# HoneyBee-V1_1.net
KiCad netlist of a schematic drawn in EAGLE
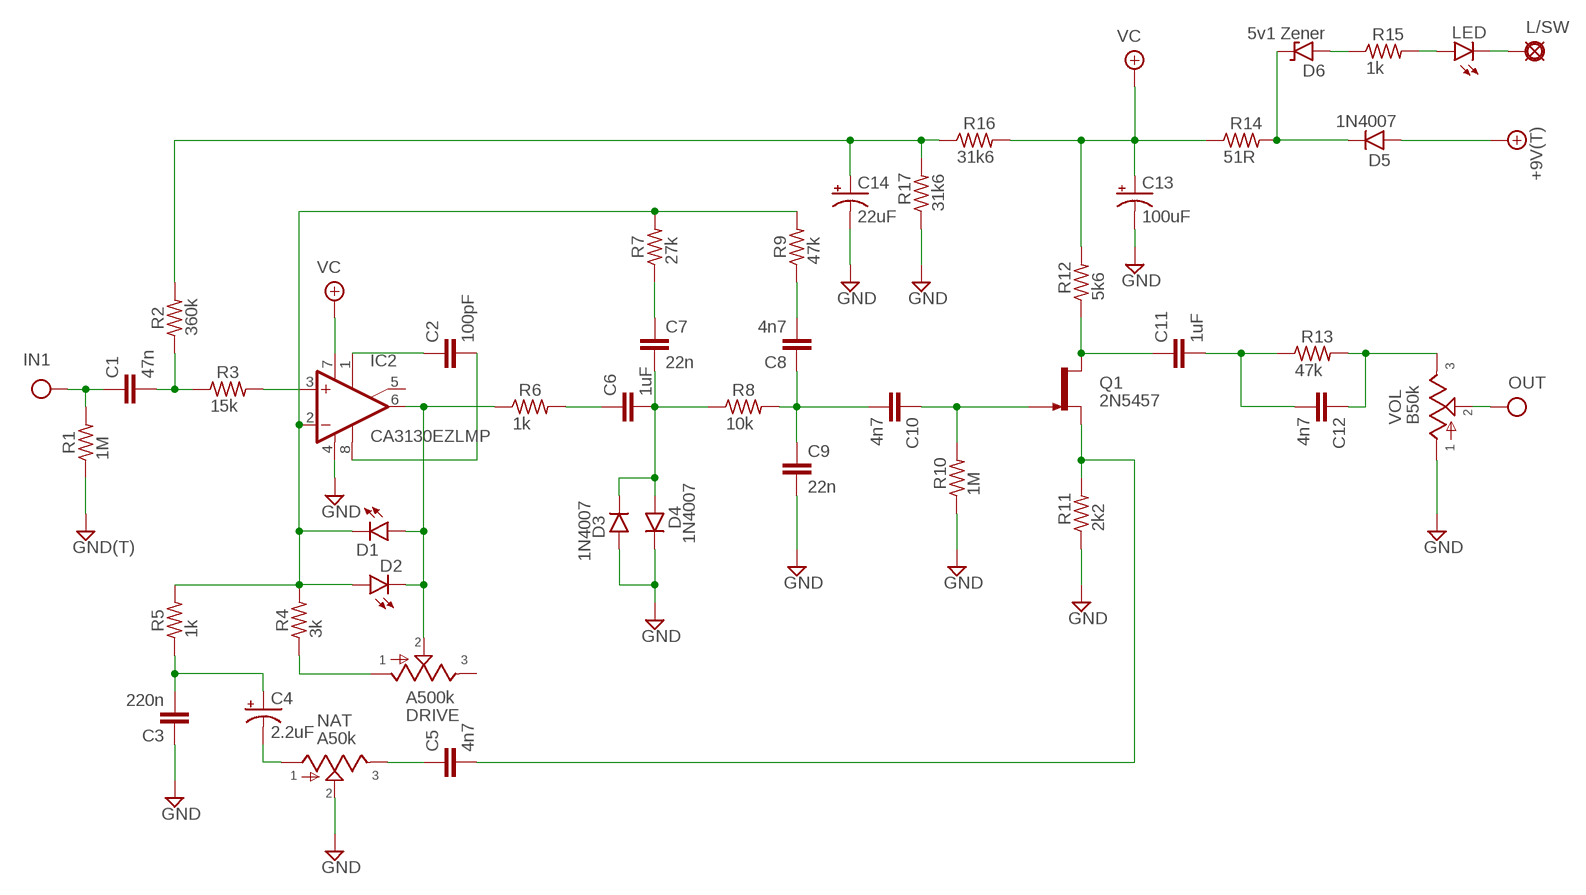
[diagram p0: schematic, sheet 1]

(export (version "E")
  (design (tool "Eeschema 10.0.6"))
  (components
    (comp (ref "+9V")
      (value "+9V(T)")
      (footprint "eagle-import:SQUARE")
      (libsource (lib "eagle-import") (part "+9V(T)"))
    )
    (comp (ref "C1")
      (value "47n")
      (footprint "eagle-import:075X040")
      (libsource (lib "eagle-import") (part "075X0402"))
    )
    (comp (ref "C2")
      (value "100pF")
      (footprint "eagle-import:050X030_025")
      (libsource (lib "eagle-import") (part "050X030_0251"))
    )
    (comp (ref "C3")
      (value "220n")
      (footprint "eagle-import:080X050")
      (libsource (lib "eagle-import") (part "080X0502"))
    )
    (comp (ref "C4")
      (value "2.2uF")
      (footprint "eagle-import:050_020_1")
      (libsource (lib "eagle-import") (part "0501"))
    )
    (comp (ref "C5")
      (value "4n7")
      (footprint "eagle-import:070X030")
      (libsource (lib "eagle-import") (part "070X0302"))
    )
    (comp (ref "C6")
      (value "1uF")
      (footprint "eagle-import:080X050")
      (libsource (lib "eagle-import") (part "080X0502"))
    )
    (comp (ref "C7")
      (value "22n")
      (footprint "eagle-import:075X030")
      (libsource (lib "eagle-import") (part "075X0302"))
    )
    (comp (ref "C8")
      (value "4n7")
      (footprint "eagle-import:070X030")
      (libsource (lib "eagle-import") (part "070X0302"))
    )
    (comp (ref "C9")
      (value "22n")
      (footprint "eagle-import:075X030")
      (libsource (lib "eagle-import") (part "075X0302"))
    )
    (comp (ref "C10")
      (value "4n7")
      (footprint "eagle-import:070X030")
      (libsource (lib "eagle-import") (part "070X0302"))
    )
    (comp (ref "C11")
      (value "1uF")
      (footprint "eagle-import:080X050")
      (libsource (lib "eagle-import") (part "080X0502"))
    )
    (comp (ref "C12")
      (value "4n7")
      (footprint "eagle-import:070X030")
      (libsource (lib "eagle-import") (part "070X0302"))
    )
    (comp (ref "C13")
      (value "100uF")
      (footprint "eagle-import:080_035_1")
      (libsource (lib "eagle-import") (part "0801"))
    )
    (comp (ref "C14")
      (value "22uF")
      (footprint "eagle-import:050_020_1")
      (libsource (lib "eagle-import") (part "0501"))
    )
    (comp (ref "D1")
      (value "LED3MM")
      (footprint "eagle-import:LED3MM")
      (libsource (lib "eagle-import") (part "LED3MM"))
    )
    (comp (ref "D2")
      (value "LED3MM")
      (footprint "eagle-import:LED3MM")
      (libsource (lib "eagle-import") (part "LED3MM"))
    )
    (comp (ref "D3")
      (value "1N4007")
      (footprint "eagle-import:DO41-3")
      (libsource (lib "eagle-import") (part "1N400X.3"))
    )
    (comp (ref "D4")
      (value "1N4007")
      (footprint "eagle-import:DO41-3")
      (libsource (lib "eagle-import") (part "1N400X.3"))
    )
    (comp (ref "D5")
      (value "1N4007")
      (footprint "eagle-import:DO41-3")
      (libsource (lib "eagle-import") (part "1N400X.3"))
    )
    (comp (ref "D6")
      (value "5v1 Zener")
      (footprint "eagle-import:DO35-3")
      (libsource (lib "eagle-import") (part "1N9ZENER"))
    )
    (comp (ref "DRIVE")
      (value "A500k")
      (footprint "eagle-import:POT")
      (libsource (lib "eagle-import") (part "POT"))
    )
    (comp (ref "G1")
      (value "GND(T)")
      (footprint "eagle-import:SQUARE")
      (libsource (lib "eagle-import") (part "GND(T)"))
    )
    (comp (ref "IC2")
      (value "CA3130EZLMP")
      (footprint "eagle-import:DIL08")
      (libsource (lib "eagle-import") (part "CA3130EZPLM"))
    )
    (comp (ref "IN1")
      (value "IN(T)")
      (footprint "eagle-import:SQUARE")
      (libsource (lib "eagle-import") (part "IN(T)"))
    )
    (comp (ref "L/SW")
      (value "PAD")
      (footprint "eagle-import:SQUARE")
      (libsource (lib "eagle-import") (part "PAD"))
    )
    (comp (ref "LED")
      (value "3mm")
      (footprint "eagle-import:LED3MM")
      (libsource (lib "eagle-import") (part "LED3MM"))
    )
    (comp (ref "NAT")
      (value "A50k")
      (footprint "eagle-import:POT")
      (libsource (lib "eagle-import") (part "POT"))
    )
    (comp (ref "OUT")
      (value "OUT(T)")
      (footprint "eagle-import:SQUARE")
      (libsource (lib "eagle-import") (part "OUT(T)"))
    )
    (comp (ref "Q1")
      (value "2N5457")
      (footprint "eagle-import:TO92-")
      (libsource (lib "eagle-import") (part "2N5457"))
    )
    (comp (ref "R1")
      (value "1M")
      (footprint "eagle-import:R0207_3")
      (libsource (lib "eagle-import") (part "6MM.3"))
    )
    (comp (ref "R2")
      (value "360k")
      (footprint "eagle-import:R0207_3")
      (libsource (lib "eagle-import") (part "6MM.3"))
    )
    (comp (ref "R3")
      (value "15k")
      (footprint "eagle-import:R0207_3")
      (libsource (lib "eagle-import") (part "6MM.3"))
    )
    (comp (ref "R4")
      (value "3k")
      (footprint "eagle-import:R0207_3")
      (libsource (lib "eagle-import") (part "6MM.3"))
    )
    (comp (ref "R5")
      (value "1k")
      (footprint "eagle-import:R0207_3")
      (libsource (lib "eagle-import") (part "6MM.3"))
    )
    (comp (ref "R6")
      (value "1k")
      (footprint "eagle-import:R0207_3")
      (libsource (lib "eagle-import") (part "6MM.3"))
    )
    (comp (ref "R7")
      (value "27k")
      (footprint "eagle-import:R0207_3")
      (libsource (lib "eagle-import") (part "6MM.3"))
    )
    (comp (ref "R8")
      (value "10k")
      (footprint "eagle-import:R0207_3")
      (libsource (lib "eagle-import") (part "6MM.3"))
    )
    (comp (ref "R9")
      (value "47k")
      (footprint "eagle-import:R0207_3")
      (libsource (lib "eagle-import") (part "6MM.3"))
    )
    (comp (ref "R10")
      (value "1M")
      (footprint "eagle-import:R0207_3")
      (libsource (lib "eagle-import") (part "6MM.3"))
    )
    (comp (ref "R11")
      (value "2k2")
      (footprint "eagle-import:R0207_3")
      (libsource (lib "eagle-import") (part "6MM.3"))
    )
    (comp (ref "R12")
      (value "5k6")
      (footprint "eagle-import:R0207_3")
      (libsource (lib "eagle-import") (part "6MM.3"))
    )
    (comp (ref "R13")
      (value "47k")
      (footprint "eagle-import:R0207_3")
      (libsource (lib "eagle-import") (part "6MM.3"))
    )
    (comp (ref "R14")
      (value "51R")
      (footprint "eagle-import:R0207_3")
      (libsource (lib "eagle-import") (part "6MM.3"))
    )
    (comp (ref "R15")
      (value "1k")
      (footprint "eagle-import:R0207_3")
      (libsource (lib "eagle-import") (part "6MM.3"))
    )
    (comp (ref "R16")
      (value "31k6")
      (footprint "eagle-import:R0207_3")
      (libsource (lib "eagle-import") (part "6MM.3"))
    )
    (comp (ref "R17")
      (value "31k6")
      (footprint "eagle-import:R0207_3")
      (libsource (lib "eagle-import") (part "6MM.3"))
    )
    (comp (ref "VOL")
      (value "B50k")
      (footprint "eagle-import:POT")
      (libsource (lib "eagle-import") (part "POT"))
    )
  )
  (nets
    (net (code "1") (name "+9V(T)") (class "Default")
      (node (ref "+9V") (pin "1") (pinfunction "+9V_1") (pintype "power_in"))
      (node (ref "D5") (pin "A") (pinfunction "A_A") (pintype "passive"))
    )
    (net (code "2") (name "GND") (class "Default")
      (node (ref "C13") (pin "-") (pinfunction "-_-") (pintype "passive"))
      (node (ref "C14") (pin "-") (pinfunction "-_-") (pintype "passive"))
      (node (ref "C3") (pin "1") (pinfunction "1_1") (pintype "passive"))
      (node (ref "C9") (pin "2") (pinfunction "2_2") (pintype "passive"))
      (node (ref "D3") (pin "A") (pinfunction "A_A") (pintype "passive"))
      (node (ref "D4") (pin "C") (pinfunction "C_C") (pintype "passive"))
      (node (ref "G1") (pin "1") (pinfunction "GND_1") (pintype "power_in"))
      (node (ref "IC2") (pin "4") (pinfunction "V-_4") (pintype "power_in"))
      (node (ref "NAT") (pin "2") (pinfunction "2_2") (pintype "passive"))
      (node (ref "R1") (pin "1") (pinfunction "1_1") (pintype "passive"))
      (node (ref "R10") (pin "1") (pinfunction "1_1") (pintype "passive"))
      (node (ref "R11") (pin "1") (pinfunction "1_1") (pintype "passive"))
      (node (ref "R17") (pin "1") (pinfunction "1_1") (pintype "passive"))
      (node (ref "VOL") (pin "1") (pinfunction "1_1") (pintype "passive"))
    )
    (net (code "3") (name "IN(T)") (class "Default")
      (node (ref "C1") (pin "1") (pinfunction "1_1") (pintype "passive"))
      (node (ref "IN1") (pin "1") (pinfunction "IN_1") (pintype "power_in"))
      (node (ref "R1") (pin "2") (pinfunction "2_2") (pintype "passive"))
    )
    (net (code "4") (name "Net-(C1-Pad2)") (class "Default")
      (node (ref "C1") (pin "2") (pinfunction "2_2") (pintype "passive"))
      (node (ref "R2") (pin "1") (pinfunction "1_1") (pintype "passive"))
      (node (ref "R3") (pin "1") (pinfunction "1_1") (pintype "passive"))
    )
    (net (code "5") (name "Net-(C3-Pad2)") (class "Default")
      (node (ref "C3") (pin "2") (pinfunction "2_2") (pintype "passive"))
      (node (ref "C4") (pin "+") (pinfunction "+_+") (pintype "passive"))
      (node (ref "R5") (pin "1") (pinfunction "1_1") (pintype "passive"))
    )
    (net (code "6") (name "Net-(C4-Pad-)") (class "Default")
      (node (ref "C4") (pin "-") (pinfunction "-_-") (pintype "passive"))
      (node (ref "NAT") (pin "1") (pinfunction "1_1") (pintype "passive"))
    )
    (net (code "7") (name "Net-(C5-Pad1)") (class "Default")
      (node (ref "C5") (pin "1") (pinfunction "1_1") (pintype "passive"))
      (node (ref "NAT") (pin "3") (pinfunction "3_3") (pintype "passive"))
    )
    (net (code "8") (name "Net-(C6-Pad1)") (class "Default")
      (node (ref "C6") (pin "1") (pinfunction "1_1") (pintype "passive"))
      (node (ref "R6") (pin "2") (pinfunction "2_2") (pintype "passive"))
    )
    (net (code "9") (name "Net-(C6-Pad2)") (class "Default")
      (node (ref "C6") (pin "2") (pinfunction "2_2") (pintype "passive"))
      (node (ref "C7") (pin "2") (pinfunction "2_2") (pintype "passive"))
      (node (ref "D3") (pin "C") (pinfunction "C_C") (pintype "passive"))
      (node (ref "D4") (pin "A") (pinfunction "A_A") (pintype "passive"))
      (node (ref "R8") (pin "1") (pinfunction "1_1") (pintype "passive"))
    )
    (net (code "10") (name "Net-(C7-Pad1)") (class "Default")
      (node (ref "C7") (pin "1") (pinfunction "1_1") (pintype "passive"))
      (node (ref "R7") (pin "1") (pinfunction "1_1") (pintype "passive"))
    )
    (net (code "11") (name "Net-(C8-Pad2)") (class "Default")
      (node (ref "C8") (pin "2") (pinfunction "2_2") (pintype "passive"))
      (node (ref "R9") (pin "1") (pinfunction "1_1") (pintype "passive"))
    )
    (net (code "12") (name "Net-(C10-Pad2)") (class "Default")
      (node (ref "C10") (pin "2") (pinfunction "2_2") (pintype "passive"))
      (node (ref "C8") (pin "1") (pinfunction "1_1") (pintype "passive"))
      (node (ref "C9") (pin "1") (pinfunction "1_1") (pintype "passive"))
      (node (ref "R8") (pin "2") (pinfunction "2_2") (pintype "passive"))
    )
    (net (code "13") (name "Net-(C11-Pad2)") (class "Default")
      (node (ref "C11") (pin "2") (pinfunction "2_2") (pintype "passive"))
      (node (ref "C12") (pin "2") (pinfunction "2_2") (pintype "passive"))
      (node (ref "R13") (pin "1") (pinfunction "1_1") (pintype "passive"))
    )
    (net (code "14") (name "Net-(C12-Pad1)") (class "Default")
      (node (ref "C12") (pin "1") (pinfunction "1_1") (pintype "passive"))
      (node (ref "R13") (pin "2") (pinfunction "2_2") (pintype "passive"))
      (node (ref "VOL") (pin "3") (pinfunction "3_3") (pintype "passive"))
    )
    (net (code "15") (name "Net-(C14-Pad+)") (class "Default")
      (node (ref "C14") (pin "+") (pinfunction "+_+") (pintype "passive"))
      (node (ref "R16") (pin "1") (pinfunction "1_1") (pintype "passive"))
      (node (ref "R17") (pin "2") (pinfunction "2_2") (pintype "passive"))
      (node (ref "R2") (pin "2") (pinfunction "2_2") (pintype "passive"))
    )
    (net (code "16") (name "Net-(D1-C)") (class "Default")
      (node (ref "D1") (pin "K") (pinfunction "C_K") (pintype "passive"))
      (node (ref "D2") (pin "A") (pinfunction "A_A") (pintype "passive"))
      (node (ref "IC2") (pin "2") (pinfunction "-IN_2") (pintype "input"))
      (node (ref "R4") (pin "2") (pinfunction "2_2") (pintype "passive"))
      (node (ref "R5") (pin "2") (pinfunction "2_2") (pintype "passive"))
      (node (ref "R7") (pin "2") (pinfunction "2_2") (pintype "passive"))
      (node (ref "R9") (pin "2") (pinfunction "2_2") (pintype "passive"))
    )
    (net (code "17") (name "Net-(D2-C)") (class "Default")
      (node (ref "D1") (pin "A") (pinfunction "A_A") (pintype "passive"))
      (node (ref "D2") (pin "K") (pinfunction "C_K") (pintype "passive"))
      (node (ref "DRIVE") (pin "2") (pinfunction "2_2") (pintype "passive"))
      (node (ref "IC2") (pin "6") (pinfunction "OUT_6") (pintype "output"))
      (node (ref "R6") (pin "1") (pinfunction "1_1") (pintype "passive"))
    )
    (net (code "18") (name "Net-(D5-PadC)") (class "Default")
      (node (ref "D5") (pin "C") (pinfunction "C_C") (pintype "passive"))
      (node (ref "D6") (pin "C") (pinfunction "C_C") (pintype "passive"))
      (node (ref "R14") (pin "2") (pinfunction "2_2") (pintype "passive"))
    )
    (net (code "19") (name "Net-(D6-PadA)") (class "Default")
      (node (ref "D6") (pin "A") (pinfunction "A_A") (pintype "passive"))
      (node (ref "R15") (pin "1") (pinfunction "1_1") (pintype "passive"))
    )
    (net (code "20") (name "Net-(DRIVE-Pad1)") (class "Default")
      (node (ref "DRIVE") (pin "1") (pinfunction "1_1") (pintype "passive"))
      (node (ref "R4") (pin "1") (pinfunction "1_1") (pintype "passive"))
    )
    (net (code "21") (name "Net-(IC2-+IN)") (class "Default")
      (node (ref "IC2") (pin "3") (pinfunction "+IN_3") (pintype "input"))
      (node (ref "R3") (pin "2") (pinfunction "2_2") (pintype "passive"))
    )
    (net (code "22") (name "Net-(IC2-ON1)") (class "Default")
      (node (ref "C2") (pin "1") (pinfunction "1_1") (pintype "passive"))
      (node (ref "IC2") (pin "1") (pinfunction "ON1_1") (pintype "passive"))
    )
    (net (code "23") (name "Net-(IC2-OPT)") (class "Default")
      (node (ref "C2") (pin "2") (pinfunction "2_2") (pintype "passive"))
      (node (ref "IC2") (pin "8") (pinfunction "OPT_8") (pintype "passive"))
    )
    (net (code "24") (name "Net-(L/SW-PAD)") (class "Default")
      (node (ref "L/SW") (pin "1") (pinfunction "PAD_1") (pintype "passive"))
      (node (ref "LED") (pin "K") (pinfunction "C_K") (pintype "passive"))
    )
    (net (code "25") (name "Net-(LED-PadA)") (class "Default")
      (node (ref "LED") (pin "A") (pinfunction "A_A") (pintype "passive"))
      (node (ref "R15") (pin "2") (pinfunction "2_2") (pintype "passive"))
    )
    (net (code "26") (name "Net-(Q1-D)") (class "Default")
      (node (ref "C11") (pin "1") (pinfunction "1_1") (pintype "passive"))
      (node (ref "Q1") (pin "3") (pinfunction "D_3") (pintype "passive"))
      (node (ref "R12") (pin "1") (pinfunction "1_1") (pintype "passive"))
    )
    (net (code "27") (name "Net-(Q1-G)") (class "Default")
      (node (ref "C10") (pin "1") (pinfunction "1_1") (pintype "passive"))
      (node (ref "Q1") (pin "1") (pinfunction "G_1") (pintype "passive"))
      (node (ref "R10") (pin "2") (pinfunction "2_2") (pintype "passive"))
    )
    (net (code "28") (name "Net-(Q1-S)") (class "Default")
      (node (ref "C5") (pin "2") (pinfunction "2_2") (pintype "passive"))
      (node (ref "Q1") (pin "2") (pinfunction "S_2") (pintype "passive"))
      (node (ref "R11") (pin "2") (pinfunction "2_2") (pintype "passive"))
    )
    (net (code "29") (name "OUT(T)") (class "Default")
      (node (ref "OUT") (pin "1") (pinfunction "OUT_1") (pintype "power_in"))
      (node (ref "VOL") (pin "2") (pinfunction "2_2") (pintype "passive"))
    )
    (net (code "30") (name "VC") (class "Default")
      (node (ref "C13") (pin "+") (pinfunction "+_+") (pintype "passive"))
      (node (ref "IC2") (pin "7") (pinfunction "V+_7") (pintype "power_in"))
      (node (ref "R12") (pin "2") (pinfunction "2_2") (pintype "passive"))
      (node (ref "R14") (pin "1") (pinfunction "1_1") (pintype "passive"))
      (node (ref "R16") (pin "2") (pinfunction "2_2") (pintype "passive"))
    )
    (net (code "31") (name "unconnected-(DRIVE-Pad3)") (class "Default")
      (node (ref "DRIVE") (pin "3") (pinfunction "3_3") (pintype "passive"))
    )
    (net (code "32") (name "unconnected-(IC2-ON2-Pad5)") (class "Default")
      (node (ref "IC2") (pin "5") (pinfunction "ON2_5") (pintype "passive"))
    )
  )
)
